# Lm317.net
KiCad netlist of a schematic drawn in EAGLE
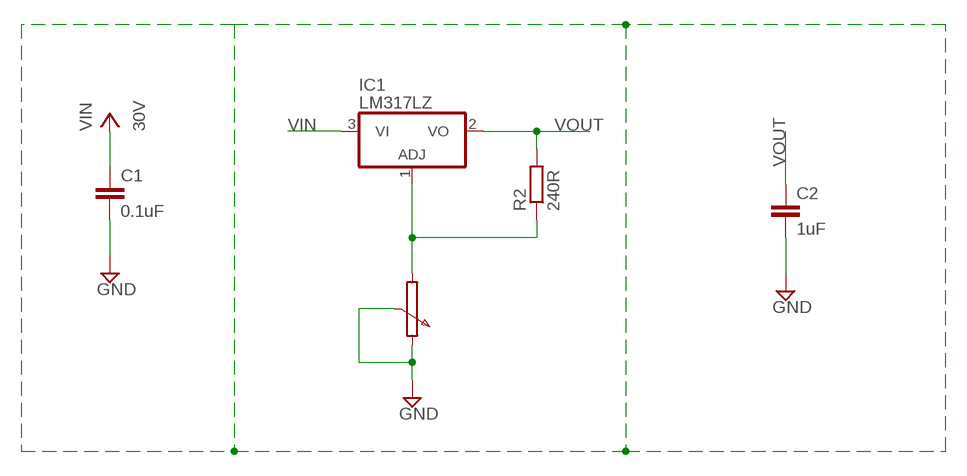
[diagram p0: schematic, sheet 1]

(export (version "E")
  (design (tool "Eeschema 10.0.6"))
  (components
    (comp (ref "C1")
      (value "0.1uF")
      (footprint "eagle-import:C050-025X075")
      (libsource (lib "eagle-import") (part "C-EU050-025X075"))
    )
    (comp (ref "C2")
      (value "1uF")
      (footprint "eagle-import:C050-025X075")
      (libsource (lib "eagle-import") (part "C-EU050-025X075"))
    )
    (comp (ref "IC1")
      (value "LM317LZ")
      (footprint "eagle-import:TO92")
      (libsource (lib "eagle-import") (part "317LZLM"))
    )
    (comp (ref "R2")
      (value "240R")
      (footprint "eagle-import:0207_10")
      (libsource (lib "eagle-import") (part "R-EU_0207/10"))
    )
  )
  (nets
    (net (code "1") (name "/VOUT") (class "Default")
      (node (ref "C2") (pin "1") (pinfunction "1_1") (pintype "passive"))
      (node (ref "IC1") (pin "2") (pinfunction "VO_2") (pintype "passive"))
      (node (ref "R2") (pin "2") (pinfunction "2_2") (pintype "passive"))
    )
    (net (code "2") (name "30V") (class "Default")
      (node (ref "C1") (pin "1") (pinfunction "1_1") (pintype "passive"))
      (node (ref "IC1") (pin "3") (pinfunction "VI_3") (pintype "input"))
    )
    (net (code "3") (name "GND") (class "Default")
      (node (ref "C1") (pin "2") (pinfunction "2_2") (pintype "passive"))
      (node (ref "C2") (pin "2") (pinfunction "2_2") (pintype "passive"))
    )
    (net (code "4") (name "Net-(IC1-ADJ)") (class "Default")
      (node (ref "IC1") (pin "1") (pinfunction "ADJ_1") (pintype "input"))
      (node (ref "R2") (pin "1") (pinfunction "1_1") (pintype "passive"))
    )
  )
)
